# PowerR2.net
KiCad netlist of a schematic drawn in Altium Designer
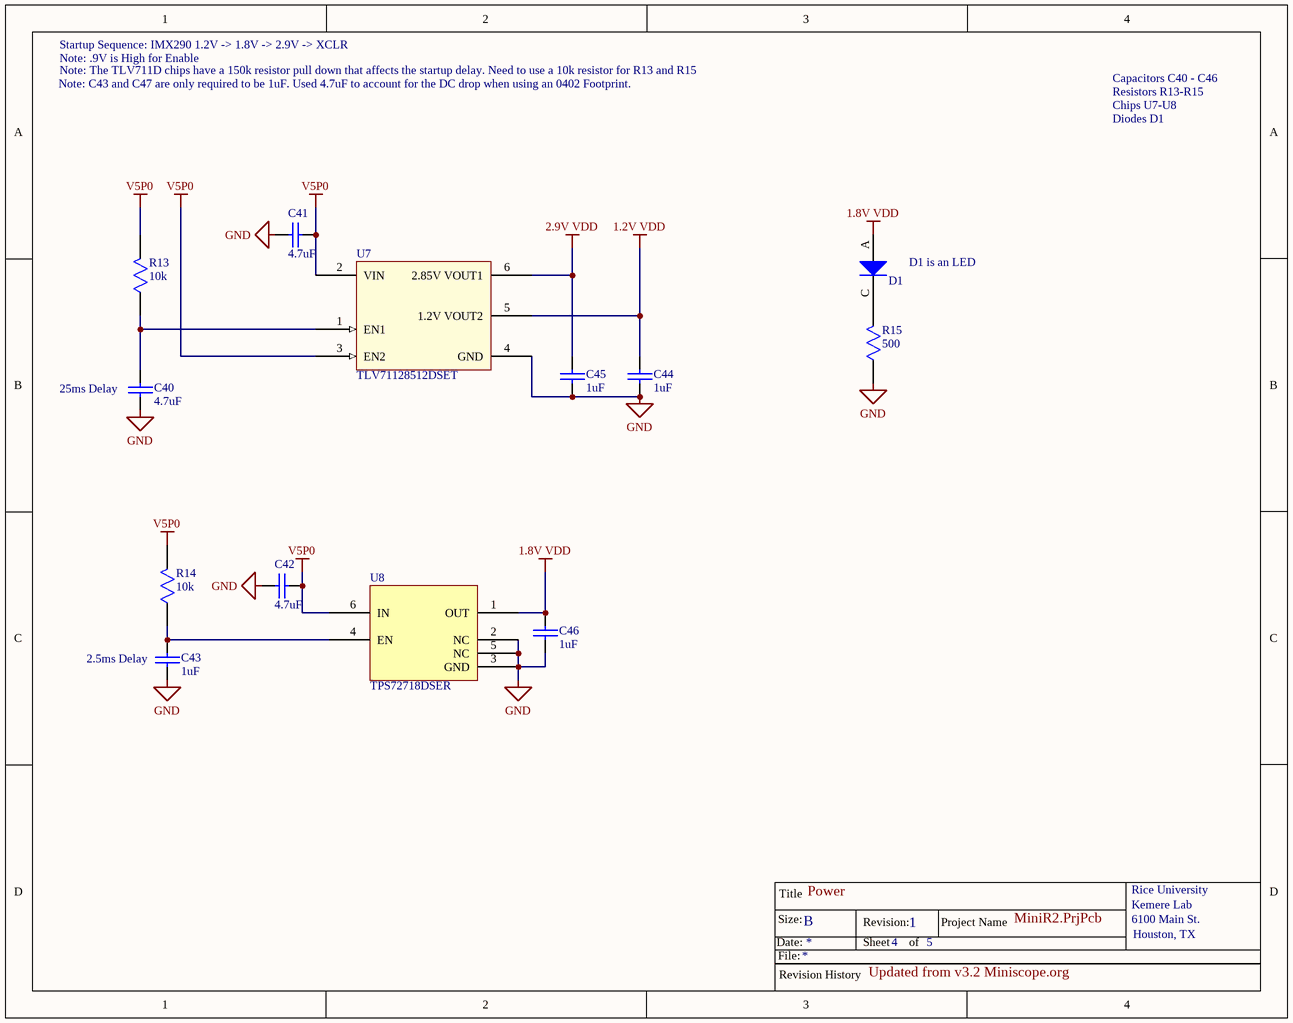
[diagram p0: PowerR2.SchDoc]

(export (version "E")
  (design (tool "Eeschema 10.0.6"))
  (components
    (comp (ref "C40")
      (value "4.7uF")
      (footprint "SMD CAP 0402")
      (libsource (lib "DA_Component_Library") (part "Capacitor"))
    )
    (comp (ref "C41")
      (value "4.7uF")
      (footprint "SMD CAP 0402")
      (libsource (lib "DA_Component_Library") (part "Capacitor"))
    )
    (comp (ref "C42")
      (value "4.7uF")
      (footprint "SMD CAP 0402")
      (libsource (lib "DA_Component_Library") (part "Capacitor"))
    )
    (comp (ref "C43")
      (value "1uF")
      (footprint "SMD CAP 0402")
      (libsource (lib "DA_Component_Library") (part "Capacitor"))
    )
    (comp (ref "C44")
      (value "1uF")
      (footprint "SMD CAP 0402")
      (libsource (lib "DA_Component_Library") (part "Capacitor"))
    )
    (comp (ref "C45")
      (value "1uF")
      (footprint "SMD CAP 0402")
      (libsource (lib "DA_Component_Library") (part "Capacitor"))
    )
    (comp (ref "C46")
      (value "1uF")
      (footprint "SMD CAP 0402")
      (libsource (lib "DA_Component_Library") (part "Capacitor"))
    )
    (comp (ref "D1")
      (value "LED 0603")
      (footprint "LED_0603")
      (description "LTST_C195TBJRKT")
      (libsource (lib "DA_Component_Library") (part "LED 0603"))
    )
    (comp (ref "R13")
      (value "10k")
      (footprint "SMD RES 0402")
      (libsource (lib "DA_Component_Library") (part "Resistor"))
    )
    (comp (ref "R14")
      (value "10k")
      (footprint "SMD RES 0402")
      (libsource (lib "DA_Component_Library") (part "Resistor"))
    )
    (comp (ref "R15")
      (value "500")
      (footprint "SMD RES 0402")
      (libsource (lib "DA_Component_Library") (part "Resistor"))
    )
    (comp (ref "U7")
      (value "TLV71128512DSET")
      (footprint "DSE")
      (description "Dual 2.85V and 1.2V Linear Regulator")
      (libsource (lib "Miniscope") (part "TLV71128512DSET"))
    )
    (comp (ref "U8")
      (value "TPS72718DSER")
      (footprint "DSE")
      (description "Single 1.8V Linear Regulator")
      (libsource (lib "Miniscope") (part "TPS72718DSER"))
    )
  )
  (nets
    (net (code "1") (name "1.2V VDD") (class "Default")
      (node (ref "C44") (pin "0") (pinfunction "0_0") (pintype "passive"))
      (node (ref "U7") (pin "5") (pinfunction "1.2V_VOUT2_5") (pintype "power_in"))
    )
    (net (code "2") (name "1.8V VDD") (class "Default")
      (node (ref "C46") (pin "1") (pinfunction "1_1") (pintype "passive"))
      (node (ref "D1") (pin "A") (pinfunction "A_A") (pintype "passive"))
      (node (ref "U8") (pin "1") (pinfunction "OUT_1") (pintype "power_in"))
    )
    (net (code "3") (name "2.9V VDD") (class "Default")
      (node (ref "C45") (pin "0") (pinfunction "0_0") (pintype "passive"))
      (node (ref "U7") (pin "6") (pinfunction "2.85V_VOUT1_6") (pintype "power_in"))
    )
    (net (code "4") (name "GND") (class "Default")
      (node (ref "C40") (pin "1") (pinfunction "1_1") (pintype "passive"))
      (node (ref "C41") (pin "1") (pinfunction "1_1") (pintype "passive"))
      (node (ref "C42") (pin "0") (pinfunction "0_0") (pintype "passive"))
      (node (ref "C43") (pin "1") (pinfunction "1_1") (pintype "passive"))
      (node (ref "C44") (pin "1") (pinfunction "1_1") (pintype "passive"))
      (node (ref "C45") (pin "1") (pinfunction "1_1") (pintype "passive"))
      (node (ref "C46") (pin "0") (pinfunction "0_0") (pintype "passive"))
      (node (ref "R15") (pin "0") (pinfunction "0_0") (pintype "passive"))
      (node (ref "U7") (pin "4") (pinfunction "GND_4") (pintype "power_in"))
      (node (ref "U8") (pin "2") (pinfunction "NC_2") (pintype "passive"))
      (node (ref "U8") (pin "3") (pinfunction "GND_3") (pintype "power_in"))
      (node (ref "U8") (pin "5") (pinfunction "NC_5") (pintype "power_in"))
    )
    (net (code "5") (name "Net-(D1-PadC)") (class "Default")
      (node (ref "D1") (pin "C") (pinfunction "C_C") (pintype "passive"))
      (node (ref "R15") (pin "1") (pinfunction "1_1") (pintype "passive"))
    )
    (net (code "6") (name "Net-(U7-EN1)") (class "Default")
      (node (ref "C40") (pin "0") (pinfunction "0_0") (pintype "passive"))
      (node (ref "R13") (pin "0") (pinfunction "0_0") (pintype "passive"))
      (node (ref "U7") (pin "1") (pinfunction "EN1_1") (pintype "input"))
    )
    (net (code "7") (name "Net-(U8-EN)") (class "Default")
      (node (ref "C43") (pin "0") (pinfunction "0_0") (pintype "passive"))
      (node (ref "R14") (pin "0") (pinfunction "0_0") (pintype "passive"))
      (node (ref "U8") (pin "4") (pinfunction "EN_4") (pintype "power_in"))
    )
    (net (code "8") (name "V5P0") (class "Default")
      (node (ref "C41") (pin "0") (pinfunction "0_0") (pintype "passive"))
      (node (ref "C42") (pin "1") (pinfunction "1_1") (pintype "passive"))
      (node (ref "R13") (pin "1") (pinfunction "1_1") (pintype "passive"))
      (node (ref "R14") (pin "1") (pinfunction "1_1") (pintype "passive"))
      (node (ref "U7") (pin "2") (pinfunction "VIN_2") (pintype "power_in"))
      (node (ref "U7") (pin "3") (pinfunction "EN2_3") (pintype "input"))
      (node (ref "U8") (pin "6") (pinfunction "IN_6") (pintype "power_in"))
    )
  )
)
